# ADC.net
KiCad netlist of a schematic drawn in Altium Designer
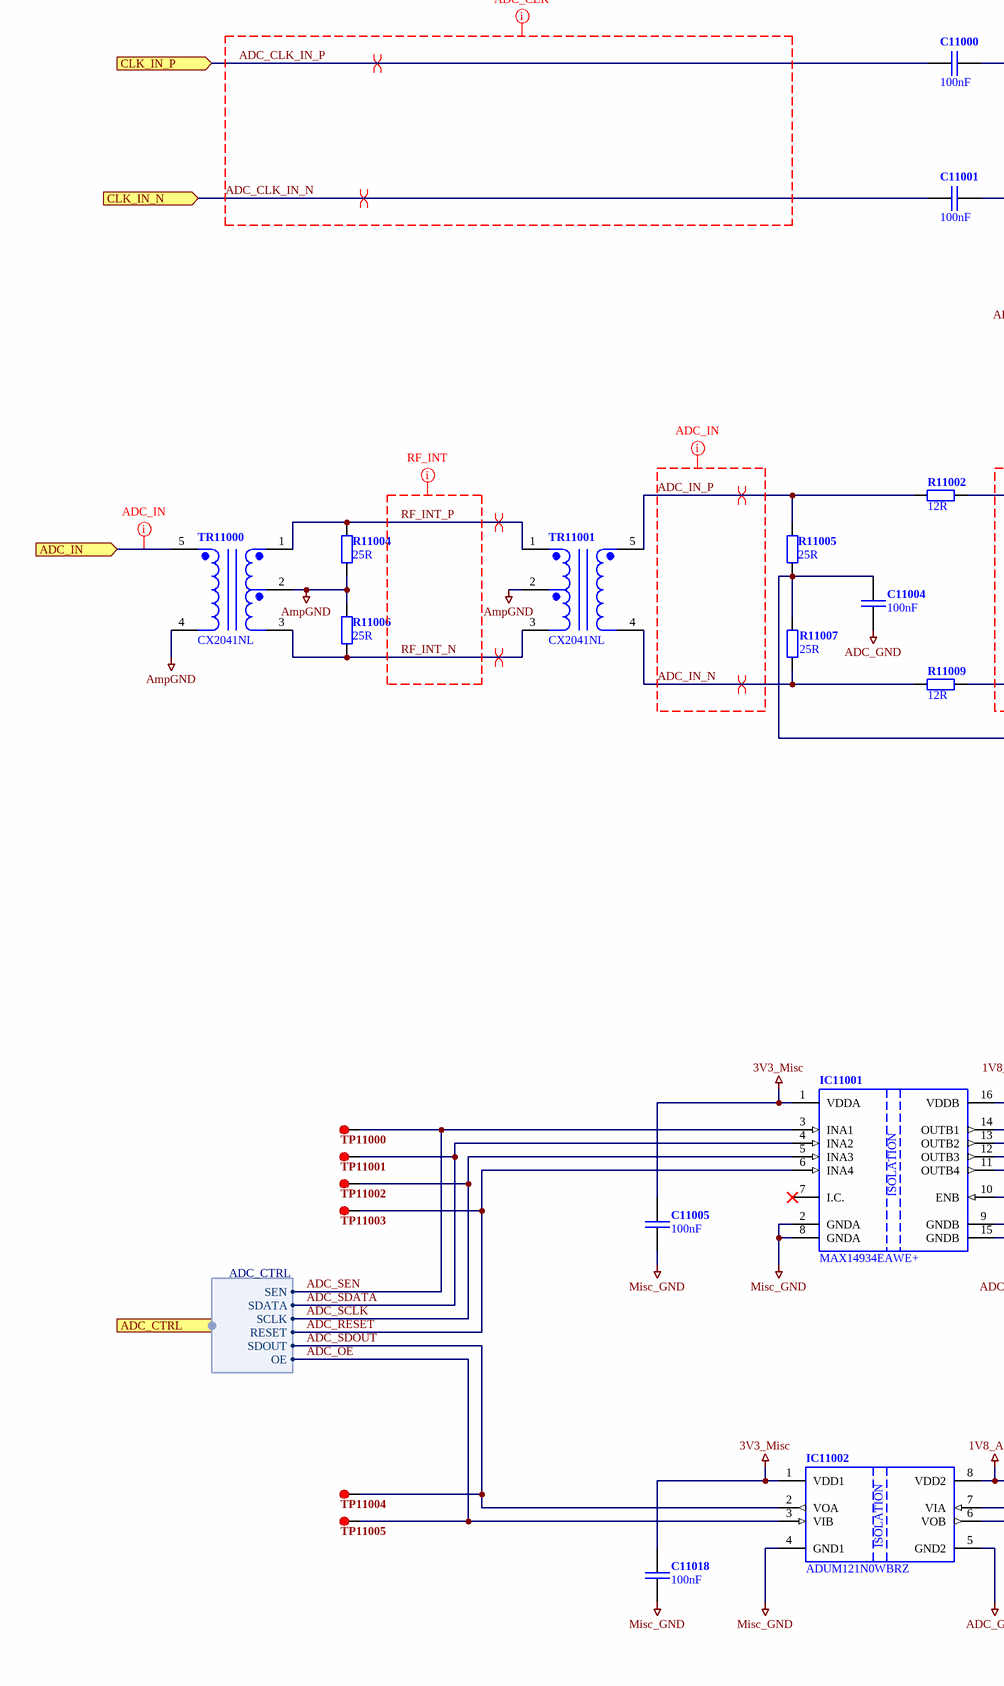
[diagram p0: ADC.SchDoc, left]
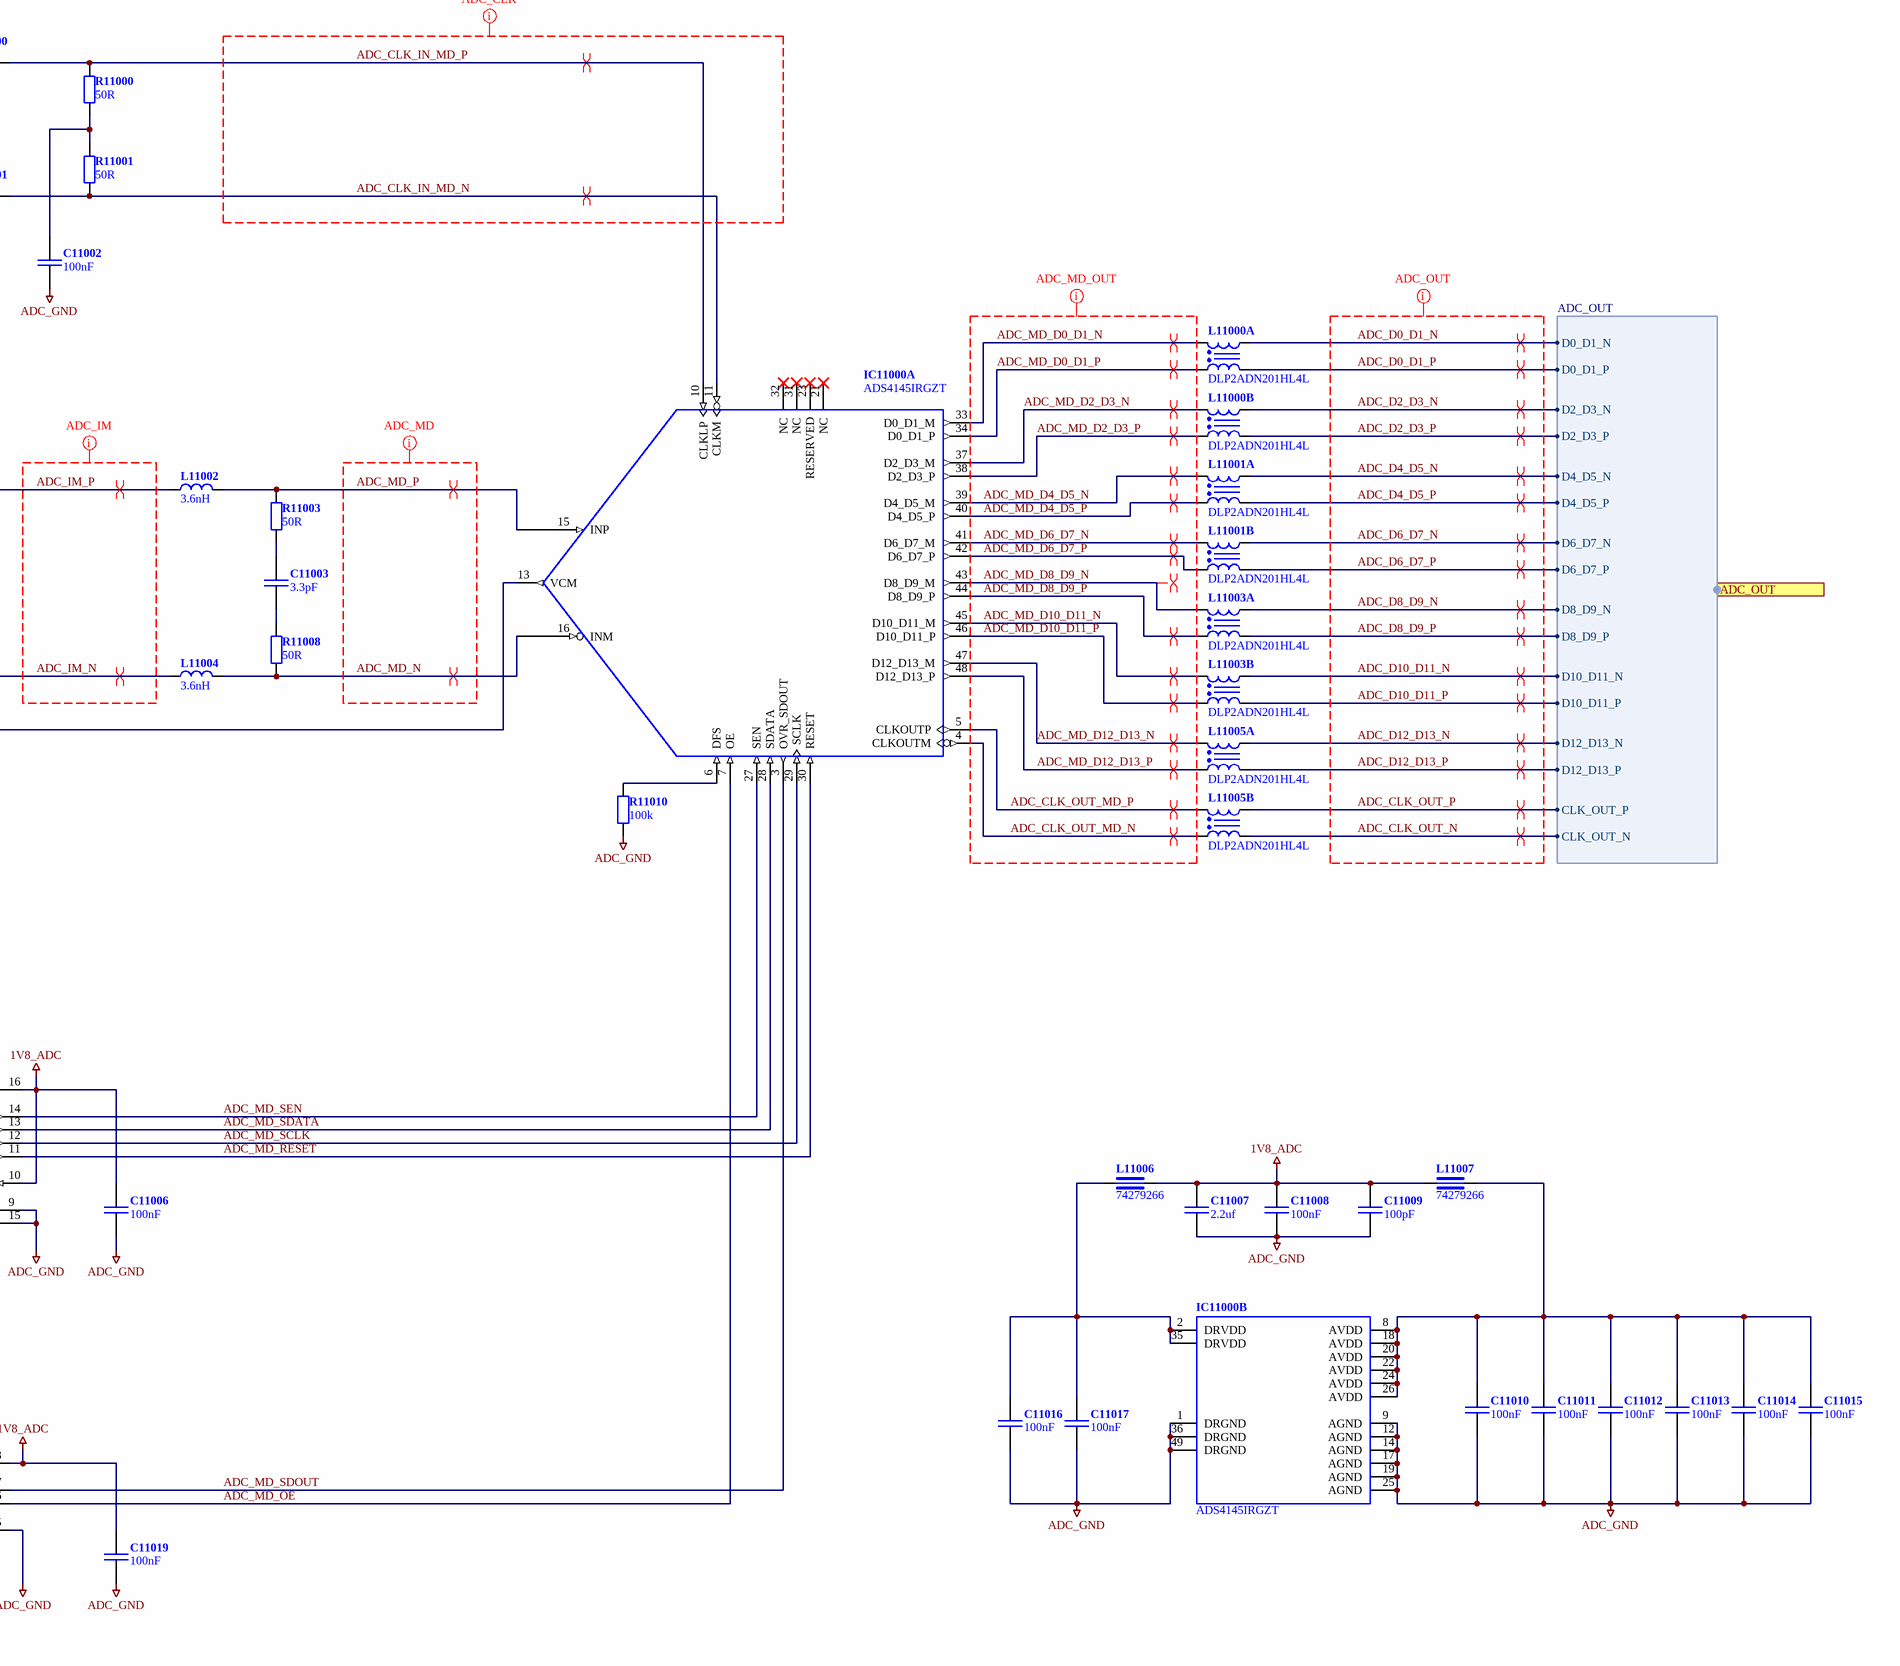
[diagram p1: ADC.SchDoc, right]

(export (version "E")
  (design (tool "Eeschema 10.0.6"))
  (components
    (comp (ref "C11000")
      (value "100nF")
      (footprint "PrometheusLib:C_0603_N [CAPC1608N IPC]")
      (libsource (lib "PrometheusLib") (part "C_GENERIC"))
    )
    (comp (ref "C11001")
      (value "100nF")
      (footprint "PrometheusLib:C_0603_N [CAPC1608N IPC]")
      (libsource (lib "PrometheusLib") (part "C_GENERIC"))
    )
    (comp (ref "C11002")
      (value "100nF")
      (footprint "PrometheusLib:C_0603_N [CAPC1608N IPC]")
      (libsource (lib "PrometheusLib") (part "C_GENERIC"))
    )
    (comp (ref "C11003")
      (value "3.3pF")
      (footprint "PrometheusLib:C_0603_N [CAPC1608N IPC]")
      (libsource (lib "PrometheusLib") (part "C_GENERIC"))
    )
    (comp (ref "C11004")
      (value "100nF")
      (footprint "PrometheusLib:C_0603_N [CAPC1608N IPC]")
      (libsource (lib "PrometheusLib") (part "C_GENERIC"))
    )
    (comp (ref "C11005")
      (value "100nF")
      (footprint "PrometheusLib:C_0603_N [CAPC1608N IPC]")
      (libsource (lib "PrometheusLib") (part "C_GENERIC"))
    )
    (comp (ref "C11006")
      (value "100nF")
      (footprint "PrometheusLib:C_0603_N [CAPC1608N IPC]")
      (libsource (lib "PrometheusLib") (part "C_GENERIC"))
    )
    (comp (ref "C11007")
      (value "2.2uf")
      (footprint "PrometheusLib:C_1206_N [CAPC3216N IPC]")
      (libsource (lib "PrometheusLib") (part "C_GENERIC"))
    )
    (comp (ref "C11008")
      (value "100nF")
      (footprint "PrometheusLib:C_0805_N [CAPC2013N IPC]")
      (libsource (lib "PrometheusLib") (part "C_GENERIC"))
    )
    (comp (ref "C11009")
      (value "100pF")
      (footprint "PrometheusLib:C_0603_N [CAPC1608N IPC]")
      (libsource (lib "PrometheusLib") (part "C_GENERIC"))
    )
    (comp (ref "C11010")
      (value "100nF")
      (footprint "PrometheusLib:C_0603_N [CAPC1608N IPC]")
      (libsource (lib "PrometheusLib") (part "C_GENERIC"))
    )
    (comp (ref "C11011")
      (value "100nF")
      (footprint "PrometheusLib:C_0603_N [CAPC1608N IPC]")
      (libsource (lib "PrometheusLib") (part "C_GENERIC"))
    )
    (comp (ref "C11012")
      (value "100nF")
      (footprint "PrometheusLib:C_0603_N [CAPC1608N IPC]")
      (libsource (lib "PrometheusLib") (part "C_GENERIC"))
    )
    (comp (ref "C11013")
      (value "100nF")
      (footprint "PrometheusLib:C_0603_N [CAPC1608N IPC]")
      (libsource (lib "PrometheusLib") (part "C_GENERIC"))
    )
    (comp (ref "C11014")
      (value "100nF")
      (footprint "PrometheusLib:C_0603_N [CAPC1608N IPC]")
      (libsource (lib "PrometheusLib") (part "C_GENERIC"))
    )
    (comp (ref "C11015")
      (value "100nF")
      (footprint "PrometheusLib:C_0603_N [CAPC1608N IPC]")
      (libsource (lib "PrometheusLib") (part "C_GENERIC"))
    )
    (comp (ref "C11016")
      (value "100nF")
      (footprint "PrometheusLib:C_0603_N [CAPC1608N IPC]")
      (libsource (lib "PrometheusLib") (part "C_GENERIC"))
    )
    (comp (ref "C11017")
      (value "100nF")
      (footprint "PrometheusLib:C_0603_N [CAPC1608N IPC]")
      (libsource (lib "PrometheusLib") (part "C_GENERIC"))
    )
    (comp (ref "C11018")
      (value "100nF")
      (footprint "PrometheusLib:C_0603_N [CAPC1608N IPC]")
      (libsource (lib "PrometheusLib") (part "C_GENERIC"))
    )
    (comp (ref "C11019")
      (value "100nF")
      (footprint "PrometheusLib:C_0603_N [CAPC1608N IPC]")
      (libsource (lib "PrometheusLib") (part "C_GENERIC"))
    )
    (comp (ref "IC11000")
      (value "ADS4145IRGZT")
      (footprint "QFN50P700X700X100_HS-49N")
      (libsource (lib "") (part "IC_ADS4145IRGZT_1"))
    )
    (comp (ref "IC11001")
      (value "MAX14934EAWE+")
      (footprint "SOIC127P1030X265-16N IPC")
      (libsource (lib "PrometheusLib") (part "IC_MAX14934EAWE+"))
    )
    (comp (ref "IC11002")
      (value "ADUM121N0WBRZ")
      (footprint "SOIC127P600X175-8N IPC")
      (description "1/1 digital isolator\r\n1.8 V to 5 V Level translation")
      (libsource (lib "PrometheusLib") (part "IC_ADUM121N0WBRZ"))
    )
    (comp (ref "L11000")
      (value "DLP2ADN201HL4L")
      (footprint "CAF-50P200X100-8N")
      (libsource (lib "") (part "L_COMMONMODE_CHOKE_DLP2ADN201HL4L_1"))
    )
    (comp (ref "L11001")
      (value "DLP2ADN201HL4L")
      (footprint "CAF-50P200X100-8N")
      (libsource (lib "PrometheusLib") (part "L_COMMONMODE_CHOKE_DLP2ADN201HL4L"))
    )
    (comp (ref "L11002")
      (value "3.6nH")
      (footprint "PrometheusLib:L_0603_N [INDC1608N IPC]")
      (fields (field (name "PROMETHEUS_MANPARTNO") "744917036"))
      (libsource (lib "PrometheusLib") (part "L_GENERIC"))
    )
    (comp (ref "L11003")
      (value "DLP2ADN201HL4L")
      (footprint "CAF-50P200X100-8N")
      (libsource (lib "PrometheusLib") (part "L_COMMONMODE_CHOKE_DLP2ADN201HL4L"))
    )
    (comp (ref "L11004")
      (value "3.6nH")
      (footprint "PrometheusLib:L_0603_N [INDC1608N IPC]")
      (fields (field (name "PROMETHEUS_MANPARTNO") "744917036"))
      (libsource (lib "PrometheusLib") (part "L_GENERIC"))
    )
    (comp (ref "L11005")
      (value "DLP2ADN201HL4L")
      (footprint "CAF-50P200X100-8N")
      (libsource (lib "PrometheusLib") (part "L_COMMONMODE_CHOKE_DLP2ADN201HL4L"))
    )
    (comp (ref "L11006")
      (value "74279266")
      (footprint "PrometheusLib:L_0603_N [INDC1608N IPC]")
      (description "1 kOHM @ 100 MHz\r\n200 mA max.")
      (libsource (lib "PrometheusLib") (part "FB_GENERIC"))
    )
    (comp (ref "L11007")
      (value "74279266")
      (footprint "PrometheusLib:L_0603_N [INDC1608N IPC]")
      (description "1 kOHM @ 100 MHz\r\n200 mA max.")
      (libsource (lib "PrometheusLib") (part "FB_GENERIC"))
    )
    (comp (ref "R11000")
      (value "50R")
      (footprint "PrometheusLib:R_0603_N [RESC1608N IPC]")
      (libsource (lib "") (part "R_GENERIC_DIN_1"))
    )
    (comp (ref "R11001")
      (value "50R")
      (footprint "PrometheusLib:R_0603_N [RESC1608N IPC]")
      (libsource (lib "") (part "R_GENERIC_DIN_1"))
    )
    (comp (ref "R11002")
      (value "12R")
      (footprint "PrometheusLib:R_0603_N [RESC1608N IPC]")
      (libsource (lib "PrometheusLib") (part "R_GENERIC_DIN"))
    )
    (comp (ref "R11003")
      (value "50R")
      (footprint "PrometheusLib:R_0603_N [RESC1608N IPC]")
      (libsource (lib "") (part "R_GENERIC_DIN_1"))
    )
    (comp (ref "R11004")
      (value "25R")
      (footprint "PrometheusLib:R_0603_N [RESC1608N IPC]")
      (libsource (lib "") (part "R_GENERIC_DIN_1"))
    )
    (comp (ref "R11005")
      (value "25R")
      (footprint "PrometheusLib:R_0603_N [RESC1608N IPC]")
      (libsource (lib "") (part "R_GENERIC_DIN_1"))
    )
    (comp (ref "R11006")
      (value "25R")
      (footprint "PrometheusLib:R_0603_N [RESC1608N IPC]")
      (libsource (lib "") (part "R_GENERIC_DIN_1"))
    )
    (comp (ref "R11007")
      (value "25R")
      (footprint "PrometheusLib:R_0603_N [RESC1608N IPC]")
      (libsource (lib "") (part "R_GENERIC_DIN_1"))
    )
    (comp (ref "R11008")
      (value "50R")
      (footprint "PrometheusLib:R_0603_N [RESC1608N IPC]")
      (libsource (lib "") (part "R_GENERIC_DIN_1"))
    )
    (comp (ref "R11009")
      (value "12R")
      (footprint "PrometheusLib:R_0603_N [RESC1608N IPC]")
      (libsource (lib "PrometheusLib") (part "R_GENERIC_DIN"))
    )
    (comp (ref "R11010")
      (value "100k")
      (footprint "PrometheusLib:R_0603_N [RESC1608N IPC]")
      (libsource (lib "") (part "R_GENERIC_DIN_1"))
    )
    (comp (ref "TP11000")
      (value "TP_GENERIC")
      (footprint "PrometheusLib:TP_0.8_P100T")
      (description "Needle Test Point")
      (libsource (lib "PrometheusLib") (part "TP_GENERIC"))
    )
    (comp (ref "TP11001")
      (value "TP_GENERIC")
      (footprint "PrometheusLib:TP_0.8_P100T")
      (description "Needle Test Point")
      (libsource (lib "PrometheusLib") (part "TP_GENERIC"))
    )
    (comp (ref "TP11002")
      (value "TP_GENERIC")
      (footprint "PrometheusLib:TP_0.8_P100T")
      (description "Needle Test Point")
      (libsource (lib "PrometheusLib") (part "TP_GENERIC"))
    )
    (comp (ref "TP11003")
      (value "TP_GENERIC")
      (footprint "PrometheusLib:TP_0.8_P100T")
      (description "Needle Test Point")
      (libsource (lib "PrometheusLib") (part "TP_GENERIC"))
    )
    (comp (ref "TP11004")
      (value "TP_GENERIC")
      (footprint "PrometheusLib:TP_0.8_P100T")
      (description "Needle Test Point")
      (libsource (lib "PrometheusLib") (part "TP_GENERIC"))
    )
    (comp (ref "TP11005")
      (value "TP_GENERIC")
      (footprint "PrometheusLib:TP_0.8_P100T")
      (description "Needle Test Point")
      (libsource (lib "PrometheusLib") (part "TP_GENERIC"))
    )
    (comp (ref "TR11000")
      (value "CX2041NL")
      (footprint "TR_CX2041NL")
      (description "Balun\r\n1:1 with center tap\r\n3 dB Bandwidth: 0.05 MHz to 450 MHz")
      (libsource (lib "") (part "TR_CX2041NL_1"))
    )
    (comp (ref "TR11001")
      (value "CX2041NL")
      (footprint "TR_CX2041NL")
      (description "Balun\r\n1:1 with center tap\r\n3 dB Bandwidth: 0.05 MHz to 450 MHz")
      (libsource (lib "PrometheusLib") (part "TR_CX2041NL"))
    )
  )
  (nets
    (net (code "3") (name "/ADC_CLK_IN_MD_N") (class "Default")
      (node (ref "C11001") (pin "1") (pintype "passive"))
      (node (ref "IC11000") (pin "11") (pinfunction "CLKM_11") (pintype "input"))
      (node (ref "R11001") (pin "1") (pinfunction "1_1") (pintype "passive"))
    )
    (net (code "4") (name "/ADC_CLK_IN_MD_P") (class "Default")
      (node (ref "C11000") (pin "1") (pintype "passive"))
      (node (ref "IC11000") (pin "10") (pinfunction "CLKLP_10") (pintype "input"))
      (node (ref "R11000") (pin "2") (pinfunction "2_2") (pintype "passive"))
    )
    (net (code "5") (name "/ADC_CLK_IN_N") (class "Default")
      (node (ref "C11001") (pin "2") (pintype "passive"))
    )
    (net (code "6") (name "/ADC_CLK_IN_P") (class "Default")
      (node (ref "C11000") (pin "2") (pintype "passive"))
    )
    (net (code "7") (name "/ADC_CLK_OUT_MD_N") (class "Default")
      (node (ref "IC11000") (pin "4") (pinfunction "CLKOUTM_4") (pintype "output"))
      (node (ref "L11005") (pin "3") (pinfunction "3_3") (pintype "passive"))
    )
    (net (code "8") (name "/ADC_CLK_OUT_MD_P") (class "Default")
      (node (ref "IC11000") (pin "5") (pinfunction "CLKOUTP_5") (pintype "output"))
      (node (ref "L11005") (pin "4") (pinfunction "4_4") (pintype "passive"))
    )
    (net (code "9") (name "/ADC_CLK_OUT_N") (class "Default")
      (node (ref "L11005") (pin "6") (pinfunction "6_6") (pintype "passive"))
    )
    (net (code "10") (name "/ADC_CLK_OUT_P") (class "Default")
      (node (ref "L11005") (pin "5") (pinfunction "5_5") (pintype "passive"))
    )
    (net (code "11") (name "/ADC_D0_D1_N") (class "Default")
      (node (ref "L11000") (pin "7") (pinfunction "7_7") (pintype "passive"))
    )
    (net (code "12") (name "/ADC_D0_D1_P") (class "Default")
      (node (ref "L11000") (pin "8") (pinfunction "8_8") (pintype "passive"))
    )
    (net (code "13") (name "/ADC_D2_D3_N") (class "Default")
      (node (ref "L11000") (pin "5") (pinfunction "5_5") (pintype "passive"))
    )
    (net (code "14") (name "/ADC_D2_D3_P") (class "Default")
      (node (ref "L11000") (pin "6") (pinfunction "6_6") (pintype "passive"))
    )
    (net (code "15") (name "/ADC_D4_D5_N") (class "Default")
      (node (ref "L11001") (pin "7") (pinfunction "7_7") (pintype "passive"))
    )
    (net (code "16") (name "/ADC_D4_D5_P") (class "Default")
      (node (ref "L11001") (pin "8") (pinfunction "8_8") (pintype "passive"))
    )
    (net (code "17") (name "/ADC_D6_D7_N") (class "Default")
      (node (ref "L11001") (pin "5") (pinfunction "5_5") (pintype "passive"))
    )
    (net (code "18") (name "/ADC_D6_D7_P") (class "Default")
      (node (ref "L11001") (pin "6") (pinfunction "6_6") (pintype "passive"))
    )
    (net (code "19") (name "/ADC_D8_D9_N") (class "Default")
      (node (ref "L11003") (pin "7") (pinfunction "7_7") (pintype "passive"))
    )
    (net (code "20") (name "/ADC_D8_D9_P") (class "Default")
      (node (ref "L11003") (pin "8") (pinfunction "8_8") (pintype "passive"))
    )
    (net (code "21") (name "/ADC_D10_D11_N") (class "Default")
      (node (ref "L11003") (pin "5") (pinfunction "5_5") (pintype "passive"))
    )
    (net (code "22") (name "/ADC_D10_D11_P") (class "Default")
      (node (ref "L11003") (pin "6") (pinfunction "6_6") (pintype "passive"))
    )
    (net (code "23") (name "/ADC_D12_D13_N") (class "Default")
      (node (ref "L11005") (pin "7") (pinfunction "7_7") (pintype "passive"))
    )
    (net (code "24") (name "/ADC_D12_D13_P") (class "Default")
      (node (ref "L11005") (pin "8") (pinfunction "8_8") (pintype "passive"))
    )
    (net (code "25") (name "/ADC_IM_N") (class "Default")
      (node (ref "L11004") (pin "1") (pinfunction "1_1") (pintype "passive"))
      (node (ref "R11009") (pin "1") (pinfunction "1_1") (pintype "passive"))
    )
    (net (code "26") (name "/ADC_IM_P") (class "Default")
      (node (ref "L11002") (pin "1") (pinfunction "1_1") (pintype "passive"))
      (node (ref "R11002") (pin "1") (pinfunction "1_1") (pintype "passive"))
    )
    (net (code "27") (name "/ADC_IN") (class "Default")
      (node (ref "TR11000") (pin "5") (pinfunction "5_5") (pintype "passive"))
    )
    (net (code "28") (name "/ADC_IN_N") (class "Default")
      (node (ref "R11007") (pin "1") (pinfunction "1_1") (pintype "passive"))
      (node (ref "R11009") (pin "2") (pinfunction "2_2") (pintype "passive"))
      (node (ref "TR11001") (pin "4") (pinfunction "4_4") (pintype "passive"))
    )
    (net (code "29") (name "/ADC_IN_P") (class "Default")
      (node (ref "R11002") (pin "2") (pinfunction "2_2") (pintype "passive"))
      (node (ref "R11005") (pin "2") (pinfunction "2_2") (pintype "passive"))
      (node (ref "TR11001") (pin "5") (pinfunction "5_5") (pintype "passive"))
    )
    (net (code "30") (name "/ADC_MD_D0_D1_N") (class "Default")
      (node (ref "IC11000") (pin "33") (pinfunction "D0_D1_M_33") (pintype "output"))
      (node (ref "L11000") (pin "2") (pinfunction "2_2") (pintype "passive"))
    )
    (net (code "31") (name "/ADC_MD_D0_D1_P") (class "Default")
      (node (ref "IC11000") (pin "34") (pinfunction "D0_D1_P_34") (pintype "output"))
      (node (ref "L11000") (pin "1") (pinfunction "1_1") (pintype "passive"))
    )
    (net (code "32") (name "/ADC_MD_D2_D3_N") (class "Default")
      (node (ref "IC11000") (pin "37") (pinfunction "D2_D3_M_37") (pintype "output"))
      (node (ref "L11000") (pin "4") (pinfunction "4_4") (pintype "passive"))
    )
    (net (code "33") (name "/ADC_MD_D2_D3_P") (class "Default")
      (node (ref "IC11000") (pin "38") (pinfunction "D2_D3_P_38") (pintype "output"))
      (node (ref "L11000") (pin "3") (pinfunction "3_3") (pintype "passive"))
    )
    (net (code "34") (name "/ADC_MD_D4_D5_N") (class "Default")
      (node (ref "IC11000") (pin "39") (pinfunction "D4_D5_M_39") (pintype "output"))
      (node (ref "L11001") (pin "2") (pinfunction "2_2") (pintype "passive"))
    )
    (net (code "35") (name "/ADC_MD_D4_D5_P") (class "Default")
      (node (ref "IC11000") (pin "40") (pinfunction "D4_D5_P_40") (pintype "output"))
      (node (ref "L11001") (pin "1") (pinfunction "1_1") (pintype "passive"))
    )
    (net (code "36") (name "/ADC_MD_D6_D7_N") (class "Default")
      (node (ref "IC11000") (pin "41") (pinfunction "D6_D7_M_41") (pintype "output"))
      (node (ref "L11001") (pin "4") (pinfunction "4_4") (pintype "passive"))
    )
    (net (code "37") (name "/ADC_MD_D6_D7_P") (class "Default")
      (node (ref "IC11000") (pin "42") (pinfunction "D6_D7_P_42") (pintype "output"))
      (node (ref "L11001") (pin "3") (pinfunction "3_3") (pintype "passive"))
    )
    (net (code "38") (name "/ADC_MD_D8_D9_N") (class "Default")
      (node (ref "IC11000") (pin "43") (pinfunction "D8_D9_M_43") (pintype "output"))
      (node (ref "L11003") (pin "2") (pinfunction "2_2") (pintype "passive"))
    )
    (net (code "39") (name "/ADC_MD_D8_D9_P") (class "Default")
      (node (ref "IC11000") (pin "44") (pinfunction "D8_D9_P_44") (pintype "output"))
      (node (ref "L11003") (pin "1") (pinfunction "1_1") (pintype "passive"))
    )
    (net (code "40") (name "/ADC_MD_D10_D11_N") (class "Default")
      (node (ref "IC11000") (pin "45") (pinfunction "D10_D11_M_45") (pintype "output"))
      (node (ref "L11003") (pin "4") (pinfunction "4_4") (pintype "passive"))
    )
    (net (code "41") (name "/ADC_MD_D10_D11_P") (class "Default")
      (node (ref "IC11000") (pin "46") (pinfunction "D10_D11_P_46") (pintype "output"))
      (node (ref "L11003") (pin "3") (pinfunction "3_3") (pintype "passive"))
    )
    (net (code "42") (name "/ADC_MD_D12_D13_N") (class "Default")
      (node (ref "IC11000") (pin "47") (pinfunction "D12_D13_M_47") (pintype "output"))
      (node (ref "L11005") (pin "2") (pinfunction "2_2") (pintype "passive"))
    )
    (net (code "43") (name "/ADC_MD_D12_D13_P") (class "Default")
      (node (ref "IC11000") (pin "48") (pinfunction "D12_D13_P_48") (pintype "output"))
      (node (ref "L11005") (pin "1") (pinfunction "1_1") (pintype "passive"))
    )
    (net (code "44") (name "/ADC_MD_N") (class "Default")
      (node (ref "IC11000") (pin "16") (pinfunction "INM_16") (pintype "input"))
      (node (ref "L11004") (pin "2") (pinfunction "2_2") (pintype "passive"))
      (node (ref "R11008") (pin "1") (pinfunction "1_1") (pintype "passive"))
    )
    (net (code "45") (name "/ADC_MD_OE") (class "Default")
      (node (ref "IC11000") (pin "7") (pinfunction "OE_7") (pintype "input"))
      (node (ref "IC11002") (pin "6") (pinfunction "VOB_6") (pintype "output"))
    )
    (net (code "46") (name "/ADC_MD_P") (class "Default")
      (node (ref "IC11000") (pin "15") (pinfunction "INP_15") (pintype "input"))
      (node (ref "L11002") (pin "2") (pinfunction "2_2") (pintype "passive"))
      (node (ref "R11003") (pin "2") (pinfunction "2_2") (pintype "passive"))
    )
    (net (code "47") (name "/ADC_MD_RESET") (class "Default")
      (node (ref "IC11000") (pin "30") (pinfunction "RESET_30") (pintype "input"))
      (node (ref "IC11001") (pin "11") (pinfunction "OUTB4_11") (pintype "output"))
    )
    (net (code "48") (name "/ADC_MD_SCLK") (class "Default")
      (node (ref "IC11000") (pin "29") (pinfunction "SCLK_29") (pintype "input"))
      (node (ref "IC11001") (pin "12") (pinfunction "OUTB3_12") (pintype "output"))
    )
    (net (code "49") (name "/ADC_MD_SDATA") (class "Default")
      (node (ref "IC11000") (pin "28") (pinfunction "SDATA_28") (pintype "input"))
      (node (ref "IC11001") (pin "13") (pinfunction "OUTB2_13") (pintype "output"))
    )
    (net (code "50") (name "/ADC_MD_SDOUT") (class "Default")
      (node (ref "IC11000") (pin "3") (pinfunction "OVR_SDOUT_3") (pintype "output"))
      (node (ref "IC11002") (pin "7") (pinfunction "VIA_7") (pintype "input"))
    )
    (net (code "51") (name "/ADC_MD_SEN") (class "Default")
      (node (ref "IC11000") (pin "27") (pinfunction "SEN_27") (pintype "input"))
      (node (ref "IC11001") (pin "14") (pinfunction "OUTB1_14") (pintype "output"))
    )
    (net (code "52") (name "/ADC_OE") (class "Default")
      (node (ref "IC11002") (pin "3") (pinfunction "VIB_3") (pintype "input"))
      (node (ref "TP11005") (pin "1") (pinfunction "1_1") (pintype "passive"))
    )
    (net (code "53") (name "/ADC_RESET") (class "Default")
      (node (ref "IC11001") (pin "6") (pinfunction "INA4_6") (pintype "input"))
      (node (ref "TP11003") (pin "1") (pinfunction "1_1") (pintype "passive"))
    )
    (net (code "54") (name "/ADC_SCLK") (class "Default")
      (node (ref "IC11001") (pin "5") (pinfunction "INA3_5") (pintype "input"))
      (node (ref "TP11002") (pin "1") (pinfunction "1_1") (pintype "passive"))
    )
    (net (code "55") (name "/ADC_SDATA") (class "Default")
      (node (ref "IC11001") (pin "4") (pinfunction "INA2_4") (pintype "input"))
      (node (ref "TP11001") (pin "1") (pinfunction "1_1") (pintype "passive"))
    )
    (net (code "56") (name "/ADC_SDOUT") (class "Default")
      (node (ref "IC11002") (pin "2") (pinfunction "VOA_2") (pintype "output"))
      (node (ref "TP11004") (pin "1") (pinfunction "1_1") (pintype "passive"))
    )
    (net (code "57") (name "/ADC_SEN") (class "Default")
      (node (ref "IC11001") (pin "3") (pinfunction "INA1_3") (pintype "input"))
      (node (ref "TP11000") (pin "1") (pinfunction "1_1") (pintype "passive"))
    )
    (net (code "58") (name "/RF_INT_N") (class "Default")
      (node (ref "R11006") (pin "1") (pinfunction "1_1") (pintype "passive"))
      (node (ref "TR11000") (pin "3") (pinfunction "3_3") (pintype "passive"))
      (node (ref "TR11001") (pin "3") (pinfunction "3_3") (pintype "passive"))
    )
    (net (code "59") (name "/RF_INT_P") (class "Default")
      (node (ref "R11004") (pin "2") (pinfunction "2_2") (pintype "passive"))
      (node (ref "TR11000") (pin "1") (pinfunction "1_1") (pintype "passive"))
      (node (ref "TR11001") (pin "1") (pinfunction "1_1") (pintype "passive"))
    )
    (net (code "62") (name "1V8_ADC") (class "Default")
      (node (ref "C11006") (pin "1") (pintype "passive"))
      (node (ref "C11007") (pin "1") (pintype "passive"))
      (node (ref "C11008") (pin "1") (pintype "passive"))
      (node (ref "C11009") (pin "1") (pintype "passive"))
      (node (ref "C11019") (pin "1") (pintype "passive"))
      (node (ref "IC11001") (pin "10") (pinfunction "ENB_10") (pintype "input"))
      (node (ref "IC11001") (pin "16") (pinfunction "VDDB_16") (pintype "passive"))
      (node (ref "IC11002") (pin "8") (pinfunction "VDD2_8") (pintype "passive"))
      (node (ref "L11006") (pin "2") (pintype "passive"))
      (node (ref "L11007") (pin "2") (pintype "passive"))
    )
    (net (code "63") (name "3V3_Misc") (class "Default")
      (node (ref "C11005") (pin "2") (pintype "passive"))
      (node (ref "C11018") (pin "2") (pintype "passive"))
      (node (ref "IC11001") (pin "1") (pinfunction "VDDA_1") (pintype "passive"))
      (node (ref "IC11002") (pin "1") (pinfunction "VDD1_1") (pintype "passive"))
    )
    (net (code "64") (name "ADC_GND") (class "Default")
      (node (ref "C11002") (pin "2") (pintype "passive"))
      (node (ref "C11004") (pin "2") (pintype "passive"))
      (node (ref "C11006") (pin "2") (pintype "passive"))
      (node (ref "C11007") (pin "2") (pintype "passive"))
      (node (ref "C11008") (pin "2") (pintype "passive"))
      (node (ref "C11009") (pin "2") (pintype "passive"))
      (node (ref "C11010") (pin "2") (pintype "passive"))
      (node (ref "C11011") (pin "2") (pintype "passive"))
      (node (ref "C11012") (pin "2") (pintype "passive"))
      (node (ref "C11013") (pin "2") (pintype "passive"))
      (node (ref "C11014") (pin "2") (pintype "passive"))
      (node (ref "C11015") (pin "2") (pintype "passive"))
      (node (ref "C11016") (pin "2") (pintype "passive"))
      (node (ref "C11017") (pin "2") (pintype "passive"))
      (node (ref "C11019") (pin "2") (pintype "passive"))
      (node (ref "IC11000") (pin "1") (pinfunction "DRGND_1") (pintype "passive"))
      (node (ref "IC11000") (pin "12") (pinfunction "AGND_12") (pintype "passive"))
      (node (ref "IC11000") (pin "14") (pinfunction "AGND_14") (pintype "passive"))
      (node (ref "IC11000") (pin "17") (pinfunction "AGND_17") (pintype "passive"))
      (node (ref "IC11000") (pin "19") (pinfunction "AGND_19") (pintype "passive"))
      (node (ref "IC11000") (pin "25") (pinfunction "AGND_25") (pintype "passive"))
      (node (ref "IC11000") (pin "36") (pinfunction "DRGND_36") (pintype "passive"))
      (node (ref "IC11000") (pin "49") (pinfunction "DRGND_49") (pintype "passive"))
      (node (ref "IC11000") (pin "9") (pinfunction "AGND_9") (pintype "passive"))
      (node (ref "IC11001") (pin "15") (pinfunction "GNDB_15") (pintype "passive"))
      (node (ref "IC11001") (pin "9") (pinfunction "GNDB_9") (pintype "passive"))
      (node (ref "IC11002") (pin "5") (pinfunction "GND2_5") (pintype "passive"))
      (node (ref "R11010") (pin "1") (pinfunction "1_1") (pintype "passive"))
    )
    (net (code "65") (name "AmpGND") (class "Default")
      (node (ref "R11004") (pin "1") (pinfunction "1_1") (pintype "passive"))
      (node (ref "R11006") (pin "2") (pinfunction "2_2") (pintype "passive"))
      (node (ref "TR11000") (pin "2") (pinfunction "2_2") (pintype "passive"))
      (node (ref "TR11000") (pin "4") (pinfunction "4_4") (pintype "passive"))
      (node (ref "TR11001") (pin "2") (pinfunction "2_2") (pintype "passive"))
    )
    (net (code "66") (name "Misc_GND") (class "Default")
      (node (ref "C11005") (pin "1") (pintype "passive"))
      (node (ref "C11018") (pin "1") (pintype "passive"))
      (node (ref "IC11001") (pin "2") (pinfunction "GNDA_2") (pintype "passive"))
      (node (ref "IC11001") (pin "8") (pinfunction "GNDA_8") (pintype "passive"))
      (node (ref "IC11002") (pin "4") (pinfunction "GND1_4") (pintype "passive"))
    )
    (net (code "67") (name "Net-(C11002-Pad1)") (class "Default")
      (node (ref "C11002") (pin "1") (pintype "passive"))
      (node (ref "R11000") (pin "1") (pinfunction "1_1") (pintype "passive"))
      (node (ref "R11001") (pin "2") (pinfunction "2_2") (pintype "passive"))
    )
    (net (code "68") (name "Net-(C11003-Pad1)") (class "Default")
      (node (ref "C11003") (pin "1") (pintype "passive"))
      (node (ref "R11003") (pin "1") (pinfunction "1_1") (pintype "passive"))
    )
    (net (code "69") (name "Net-(C11003-Pad2)") (class "Default")
      (node (ref "C11003") (pin "2") (pintype "passive"))
      (node (ref "R11008") (pin "2") (pinfunction "2_2") (pintype "passive"))
    )
    (net (code "70") (name "Net-(C11010-Pad1)") (class "Default")
      (node (ref "C11010") (pin "1") (pintype "passive"))
      (node (ref "C11011") (pin "1") (pintype "passive"))
      (node (ref "C11012") (pin "1") (pintype "passive"))
      (node (ref "C11013") (pin "1") (pintype "passive"))
      (node (ref "C11014") (pin "1") (pintype "passive"))
      (node (ref "C11015") (pin "1") (pintype "passive"))
      (node (ref "IC11000") (pin "18") (pinfunction "AVDD_18") (pintype "passive"))
      (node (ref "IC11000") (pin "20") (pinfunction "AVDD_20") (pintype "passive"))
      (node (ref "IC11000") (pin "22") (pinfunction "AVDD_22") (pintype "passive"))
      (node (ref "IC11000") (pin "24") (pinfunction "AVDD_24") (pintype "passive"))
      (node (ref "IC11000") (pin "26") (pinfunction "AVDD_26") (pintype "passive"))
      (node (ref "IC11000") (pin "8") (pinfunction "AVDD_8") (pintype "passive"))
      (node (ref "L11007") (pin "1") (pintype "passive"))
    )
    (net (code "71") (name "Net-(C11016-Pad1)") (class "Default")
      (node (ref "C11016") (pin "1") (pintype "passive"))
      (node (ref "C11017") (pin "1") (pintype "passive"))
      (node (ref "IC11000") (pin "2") (pinfunction "DRVDD_2") (pintype "passive"))
      (node (ref "IC11000") (pin "35") (pinfunction "DRVDD_35") (pintype "passive"))
      (node (ref "L11006") (pin "1") (pintype "passive"))
    )
    (net (code "72") (name "Net-(IC11000A-DFS)") (class "Default")
      (node (ref "IC11000") (pin "6") (pinfunction "DFS_6") (pintype "input"))
      (node (ref "R11010") (pin "2") (pinfunction "2_2") (pintype "passive"))
    )
    (net (code "73") (name "Net-(IC11000A-VCM)") (class "Default")
      (node (ref "C11004") (pin "1") (pintype "passive"))
      (node (ref "IC11000") (pin "13") (pinfunction "VCM_13") (pintype "output"))
      (node (ref "R11005") (pin "1") (pinfunction "1_1") (pintype "passive"))
      (node (ref "R11007") (pin "2") (pinfunction "2_2") (pintype "passive"))
    )
    (net (code "74") (name "unconnected-(IC11000A-NC-Pad21)") (class "Default")
      (node (ref "IC11000") (pin "21") (pinfunction "NC_21") (pintype "passive+no_connect"))
    )
    (net (code "75") (name "unconnected-(IC11000A-NC-Pad31)") (class "Default")
      (node (ref "IC11000") (pin "31") (pinfunction "NC_31") (pintype "passive+no_connect"))
    )
    (net (code "76") (name "unconnected-(IC11000A-NC-Pad32)") (class "Default")
      (node (ref "IC11000") (pin "32") (pinfunction "NC_32") (pintype "passive+no_connect"))
    )
    (net (code "77") (name "unconnected-(IC11000A-RESERVED-Pad23)") (class "Default")
      (node (ref "IC11000") (pin "23") (pinfunction "RESERVED_23") (pintype "passive+no_connect"))
    )
    (net (code "78") (name "unconnected-(IC11001-I.C.-Pad7)") (class "Default")
      (node (ref "IC11001") (pin "7") (pinfunction "I.C._7") (pintype "passive+no_connect"))
    )
  )
)
